# xiao-extension.net
KiCad netlist of a schematic drawn in EAGLE
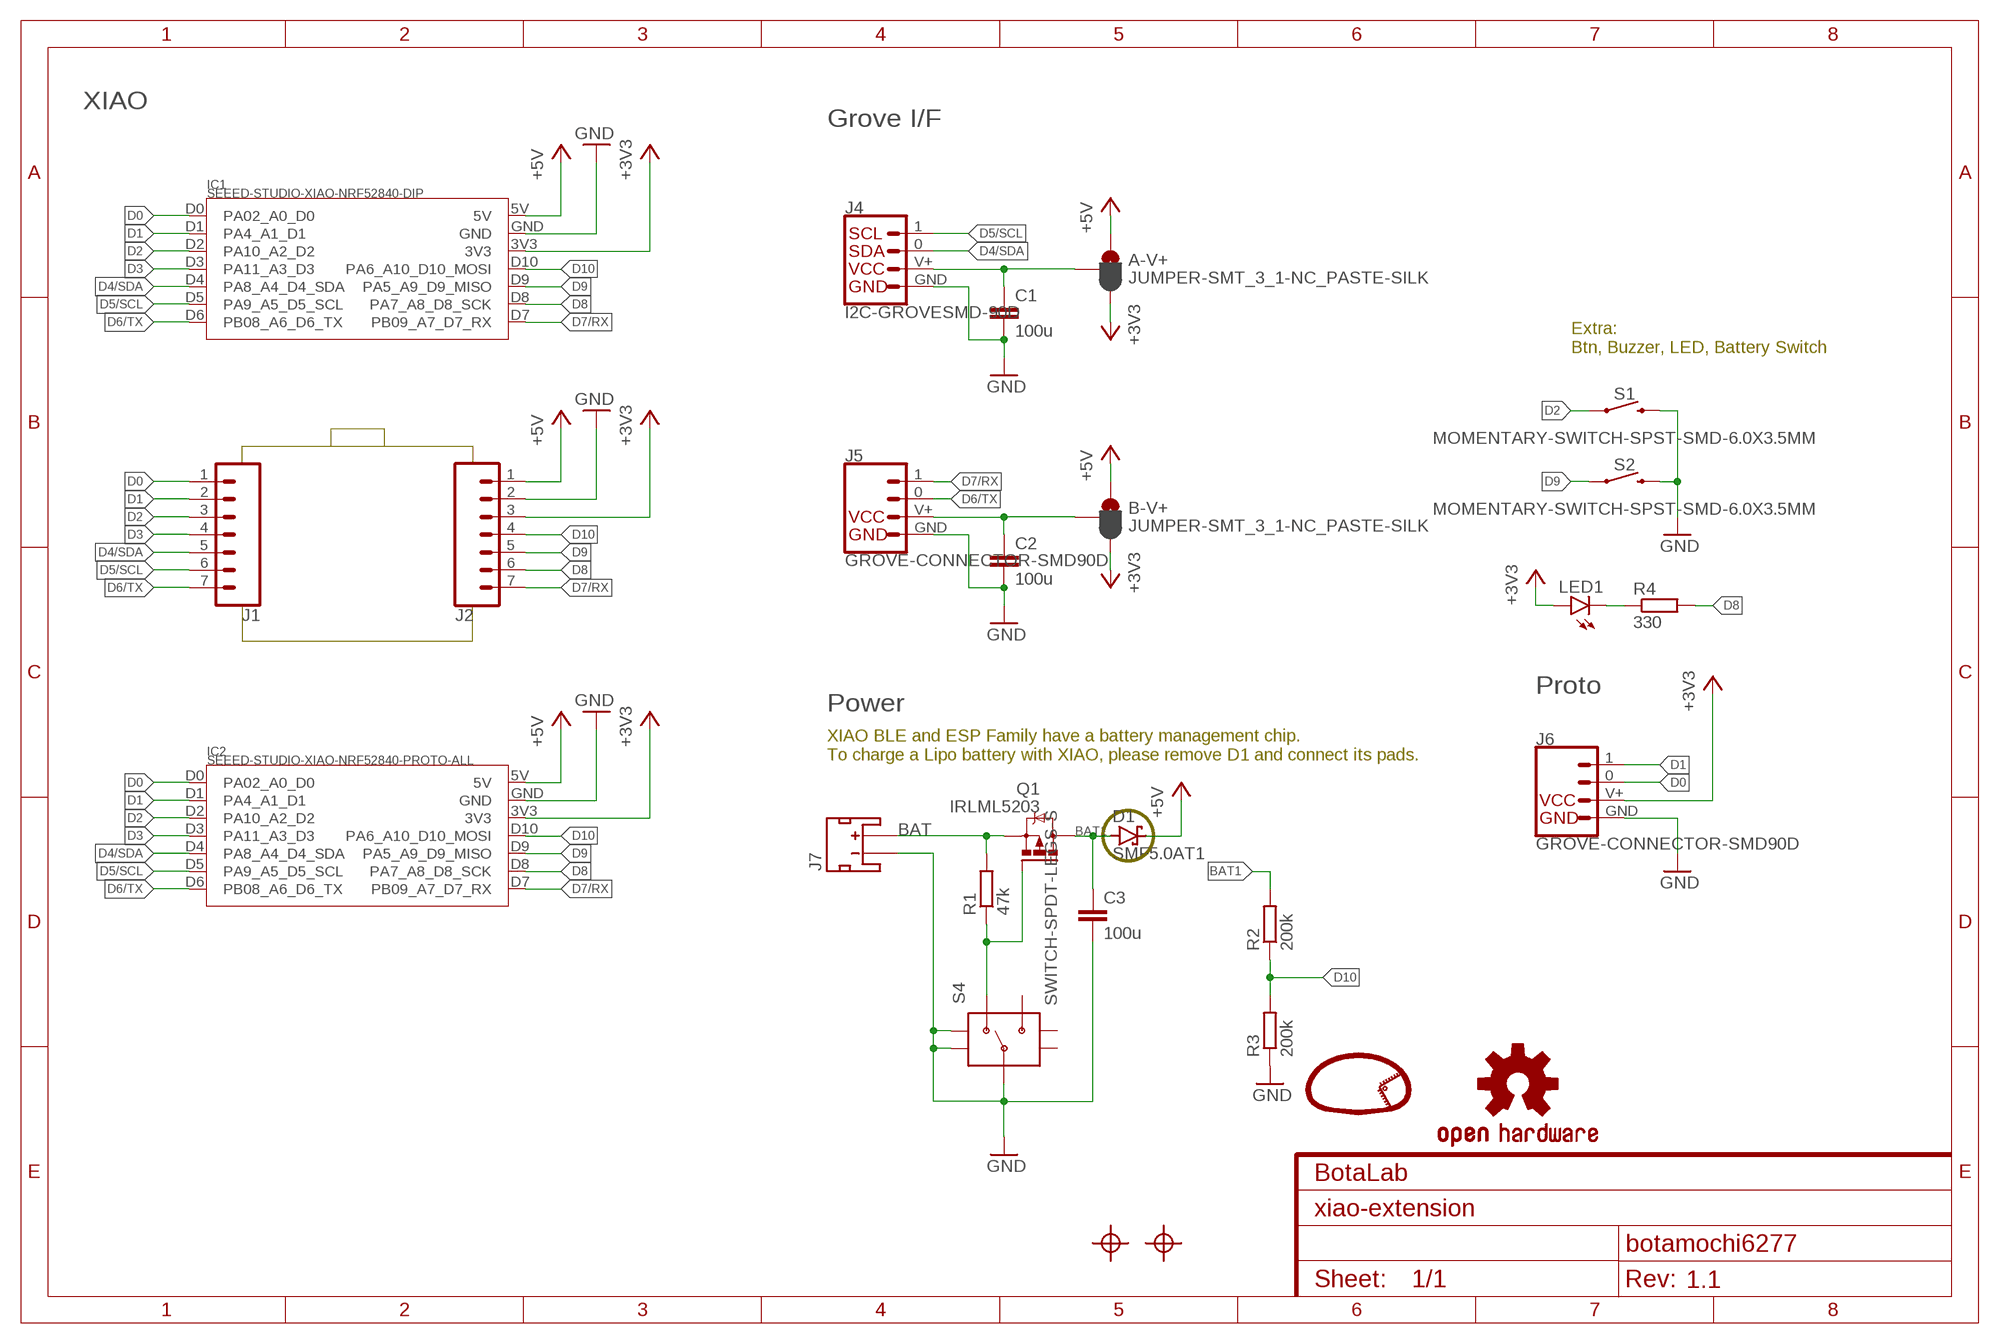
[diagram p0: schematic, sheet 1]

(export (version "E")
  (design (tool "Eeschema 10.0.6"))
  (components
    (comp (ref "A-V+")
      (value "JUMPER-SMT_3_1-NC_PASTE-SILK")
      (footprint "eagle-import:SMT-JUMPER_3_1-NC_PASTE_SILK")
      (libsource (lib "eagle-import") (part "JUMPER-SMT_3_1-NC_PASTE-SILK"))
    )
    (comp (ref "B-V+")
      (value "JUMPER-SMT_3_1-NC_PASTE-SILK")
      (footprint "eagle-import:SMT-JUMPER_3_1-NC_PASTE_SILK")
      (libsource (lib "eagle-import") (part "JUMPER-SMT_3_1-NC_PASTE-SILK"))
    )
    (comp (ref "C1")
      (value "100u")
      (footprint "eagle-import:C3216")
      (libsource (lib "eagle-import") (part "C-EUC3216"))
    )
    (comp (ref "C2")
      (value "100u")
      (footprint "eagle-import:C3216")
      (libsource (lib "eagle-import") (part "C-EUC3216"))
    )
    (comp (ref "C3")
      (value "100u")
      (footprint "eagle-import:C3216")
      (libsource (lib "eagle-import") (part "C-EUC3216"))
    )
    (comp (ref "D1")
      (value "SMF5.0AT1")
      (footprint "eagle-import:SOD123FL")
      (libsource (lib "eagle-import") (part "SMF5.0AT1"))
    )
    (comp (ref "H1")
      (value "HOLE-SILK-2.1")
      (footprint "eagle-import:MOUNTING_HOLE_SILK_2.1")
      (libsource (lib "eagle-import") (part "HOLE-SILK-2.1"))
    )
    (comp (ref "H2")
      (value "HOLE-SILK-2.1")
      (footprint "eagle-import:MOUNTING_HOLE_SILK_2.1")
      (libsource (lib "eagle-import") (part "HOLE-SILK-2.1"))
    )
    (comp (ref "IC1")
      (value "SEEED-STUDIO-XIAO-NRF52840-DIP")
      (footprint "eagle-import:XIAO-NRF52840-DIP")
      (libsource (lib "eagle-import") (part "SEEED-STUDIO-XIAO-NRF52840-DIP"))
    )
    (comp (ref "IC2")
      (value "SEEED-STUDIO-XIAO-NRF52840-PROTO-ALL")
      (footprint "eagle-import:XIAO-SMD-PROTO")
      (libsource (lib "eagle-import") (part "SEEED-STUDIO-XIAO-NRF52840-PROTO-ALL"))
    )
    (comp (ref "J1")
      (value "CONN_07NO_SILK")
      (footprint "eagle-import:1X07_NO_SILK")
      (libsource (lib "eagle-import") (part "CONN_07NO_SILK"))
    )
    (comp (ref "J2")
      (value "CONN_07NO_SILK")
      (footprint "eagle-import:1X07_NO_SILK")
      (libsource (lib "eagle-import") (part "CONN_07NO_SILK"))
    )
    (comp (ref "J4")
      (value "I2C-GROVESMD-90D")
      (footprint "eagle-import:HW4-SMD-2.0-90D")
      (libsource (lib "eagle-import") (part "I2C-GROVESMD-90D"))
    )
    (comp (ref "J5")
      (value "GROVE-CONNECTOR-SMD90D")
      (footprint "eagle-import:HW4-SMD-2.0-90D")
      (libsource (lib "eagle-import") (part "GROVE-CONNECTOR-SMD90D"))
    )
    (comp (ref "J6")
      (value "GROVE-CONNECTOR-SMD90D")
      (footprint "eagle-import:HW4-SMD-2.0-90D")
      (libsource (lib "eagle-import") (part "GROVE-CONNECTOR-SMD90D"))
    )
    (comp (ref "J7")
      (value "JST_2MM_MALE")
      (footprint "eagle-import:JST-2-SMD")
      (libsource (lib "eagle-import") (part "JST_2MM_MALE"))
    )
    (comp (ref "LED1")
      (value "LEDCHIP-LED0603")
      (footprint "eagle-import:CHIP-LED0603")
      (libsource (lib "eagle-import") (part "LEDCHIP-LED0603"))
    )
    (comp (ref "LOGO1")
      (value "LOGO")
      (footprint "eagle-import:LOGO")
      (libsource (lib "eagle-import") (part "LOGO"))
    )
    (comp (ref "LOGO2")
      (value "OSHW-LOGOS")
      (footprint "eagle-import:OSHW-LOGO-S")
      (libsource (lib "eagle-import") (part "OSHW-LOGOS"))
    )
    (comp (ref "Q1")
      (value "IRLML5203")
      (footprint "eagle-import:MICRO3")
      (libsource (lib "eagle-import") (part "IRLML5203"))
    )
    (comp (ref "R1")
      (value "47k")
      (footprint "eagle-import:R0603")
      (libsource (lib "eagle-import") (part "R-EU_R0603"))
    )
    (comp (ref "R2")
      (value "200k")
      (footprint "eagle-import:R0603")
      (libsource (lib "eagle-import") (part "R-EU_R0603"))
    )
    (comp (ref "R3")
      (value "200k")
      (footprint "eagle-import:R0603")
      (libsource (lib "eagle-import") (part "R-EU_R0603"))
    )
    (comp (ref "R4")
      (value "330")
      (footprint "eagle-import:R0603")
      (libsource (lib "eagle-import") (part "R-EU_R0603"))
    )
    (comp (ref "S1")
      (value "MOMENTARY-SWITCH-SPST-SMD-6.0X3.5MM")
      (footprint "eagle-import:TACTILE_SWITCH_SMD_6.0X3.5MM")
      (libsource (lib "eagle-import") (part "MOMENTARY-SWITCH-SPST-SMD-6.0X3.5MM"))
    )
    (comp (ref "S2")
      (value "MOMENTARY-SWITCH-SPST-SMD-6.0X3.5MM")
      (footprint "eagle-import:TACTILE_SWITCH_SMD_6.0X3.5MM")
      (libsource (lib "eagle-import") (part "MOMENTARY-SWITCH-SPST-SMD-6.0X3.5MM"))
    )
    (comp (ref "S4")
      (value "SWITCH-SPDT-LEGS-S")
      (footprint "eagle-import:SWITCH_SPST_SMD_A")
      (libsource (lib "eagle-import") (part "SWITCH-SPDT-LEGS-S"))
    )
  )
  (nets
    (net (code "1") (name "+3V3") (class "Default")
      (node (ref "A-V+") (pin "3") (pinfunction "3_3") (pintype "passive"))
      (node (ref "B-V+") (pin "3") (pinfunction "3_3") (pintype "passive"))
      (node (ref "IC1") (pin "3V3") (pinfunction "3V3_3V3") (pintype "bidirectional"))
      (node (ref "IC2") (pin "3V3") (pinfunction "3V3_3V3") (pintype "bidirectional"))
      (node (ref "J2") (pin "3") (pinfunction "3_3") (pintype "passive"))
      (node (ref "J6") (pin "V+") (pinfunction "VCC_V+") (pintype "power_in"))
      (node (ref "LED1") (pin "A") (pinfunction "A_A") (pintype "passive"))
    )
    (net (code "2") (name "+5V") (class "Default")
      (node (ref "A-V+") (pin "1") (pinfunction "1_1") (pintype "passive"))
      (node (ref "B-V+") (pin "1") (pinfunction "1_1") (pintype "passive"))
      (node (ref "D1") (pin "C") (pinfunction "C_C") (pintype "passive"))
      (node (ref "IC1") (pin "5V") (pinfunction "5V_5V") (pintype "bidirectional"))
      (node (ref "IC2") (pin "5V") (pinfunction "5V_5V") (pintype "bidirectional"))
      (node (ref "J2") (pin "1") (pinfunction "1_1") (pintype "passive"))
    )
    (net (code "3") (name "/BAT") (class "Default")
      (node (ref "J7") (pin "2") (pinfunction "+_2") (pintype "bidirectional"))
      (node (ref "Q1") (pin "2") (pinfunction "S_2") (pintype "passive"))
      (node (ref "R1") (pin "2") (pinfunction "2_2") (pintype "passive"))
    )
    (net (code "4") (name "BAT1") (class "Default")
      (node (ref "C3") (pin "1") (pinfunction "1_1") (pintype "passive"))
      (node (ref "D1") (pin "A") (pinfunction "A_A") (pintype "passive"))
      (node (ref "Q1") (pin "3") (pinfunction "D_3") (pintype "passive"))
      (node (ref "R2") (pin "2") (pinfunction "2_2") (pintype "passive"))
    )
    (net (code "5") (name "D0") (class "Default")
      (node (ref "IC1") (pin "D0") (pinfunction "PA02_A0_D0_D0") (pintype "bidirectional"))
      (node (ref "IC2") (pin "D0") (pinfunction "PA02_A0_D0_D0") (pintype "bidirectional"))
      (node (ref "J1") (pin "1") (pinfunction "1_1") (pintype "passive"))
      (node (ref "J6") (pin "0") (pinfunction "3_0") (pintype "passive"))
    )
    (net (code "6") (name "D1") (class "Default")
      (node (ref "IC1") (pin "D1") (pinfunction "PA4_A1_D1_D1") (pintype "bidirectional"))
      (node (ref "IC2") (pin "D1") (pinfunction "PA4_A1_D1_D1") (pintype "bidirectional"))
      (node (ref "J1") (pin "2") (pinfunction "2_2") (pintype "passive"))
      (node (ref "J6") (pin "1") (pinfunction "4_1") (pintype "passive"))
    )
    (net (code "7") (name "D2") (class "Default")
      (node (ref "IC1") (pin "D2") (pinfunction "PA10_A2_D2_D2") (pintype "bidirectional"))
      (node (ref "IC2") (pin "D2") (pinfunction "PA10_A2_D2_D2") (pintype "bidirectional"))
      (node (ref "J1") (pin "3") (pinfunction "3_3") (pintype "passive"))
      (node (ref "S1") (pin "1") (pinfunction "1_1") (pintype "passive"))
    )
    (net (code "8") (name "D3") (class "Default")
      (node (ref "IC1") (pin "D3") (pinfunction "PA11_A3_D3_D3") (pintype "bidirectional"))
      (node (ref "IC2") (pin "D3") (pinfunction "PA11_A3_D3_D3") (pintype "bidirectional"))
      (node (ref "J1") (pin "4") (pinfunction "4_4") (pintype "passive"))
    )
    (net (code "9") (name "D4{slash}SDA") (class "Default")
      (node (ref "IC1") (pin "D4") (pinfunction "PA8_A4_D4_SDA_D4") (pintype "bidirectional"))
      (node (ref "IC2") (pin "D4") (pinfunction "PA8_A4_D4_SDA_D4") (pintype "bidirectional"))
      (node (ref "J1") (pin "5") (pinfunction "5_5") (pintype "passive"))
      (node (ref "J4") (pin "0") (pinfunction "3_0") (pintype "passive"))
    )
    (net (code "10") (name "D5{slash}SCL") (class "Default")
      (node (ref "IC1") (pin "D5") (pinfunction "PA9_A5_D5_SCL_D5") (pintype "bidirectional"))
      (node (ref "IC2") (pin "D5") (pinfunction "PA9_A5_D5_SCL_D5") (pintype "bidirectional"))
      (node (ref "J1") (pin "6") (pinfunction "6_6") (pintype "passive"))
      (node (ref "J4") (pin "1") (pinfunction "4_1") (pintype "passive"))
    )
    (net (code "11") (name "D6{slash}TX") (class "Default")
      (node (ref "IC1") (pin "D6") (pinfunction "PB08_A6_D6_TX_D6") (pintype "bidirectional"))
      (node (ref "IC2") (pin "D6") (pinfunction "PB08_A6_D6_TX_D6") (pintype "bidirectional"))
      (node (ref "J1") (pin "7") (pinfunction "7_7") (pintype "passive"))
      (node (ref "J5") (pin "0") (pinfunction "3_0") (pintype "passive"))
    )
    (net (code "12") (name "D7{slash}RX") (class "Default")
      (node (ref "IC1") (pin "D7") (pinfunction "PB09_A7_D7_RX_D7") (pintype "bidirectional"))
      (node (ref "IC2") (pin "D7") (pinfunction "PB09_A7_D7_RX_D7") (pintype "bidirectional"))
      (node (ref "J2") (pin "7") (pinfunction "7_7") (pintype "passive"))
      (node (ref "J5") (pin "1") (pinfunction "4_1") (pintype "passive"))
    )
    (net (code "13") (name "D8") (class "Default")
      (node (ref "IC1") (pin "D8") (pinfunction "PA7_A8_D8_SCK_D8") (pintype "bidirectional"))
      (node (ref "IC2") (pin "D8") (pinfunction "PA7_A8_D8_SCK_D8") (pintype "bidirectional"))
      (node (ref "J2") (pin "6") (pinfunction "6_6") (pintype "passive"))
      (node (ref "R4") (pin "2") (pinfunction "2_2") (pintype "passive"))
    )
    (net (code "14") (name "D9") (class "Default")
      (node (ref "IC1") (pin "D9") (pinfunction "PA5_A9_D9_MISO_D9") (pintype "bidirectional"))
      (node (ref "IC2") (pin "D9") (pinfunction "PA5_A9_D9_MISO_D9") (pintype "bidirectional"))
      (node (ref "J2") (pin "5") (pinfunction "5_5") (pintype "passive"))
      (node (ref "S2") (pin "1") (pinfunction "1_1") (pintype "passive"))
    )
    (net (code "15") (name "D10") (class "Default")
      (node (ref "IC1") (pin "D10") (pinfunction "PA6_A10_D10_MOSI_D10") (pintype "bidirectional"))
      (node (ref "IC2") (pin "D10") (pinfunction "PA6_A10_D10_MOSI_D10") (pintype "bidirectional"))
      (node (ref "J2") (pin "4") (pinfunction "4_4") (pintype "passive"))
      (node (ref "R2") (pin "1") (pinfunction "1_1") (pintype "passive"))
      (node (ref "R3") (pin "2") (pinfunction "2_2") (pintype "passive"))
    )
    (net (code "16") (name "GND") (class "Default")
      (node (ref "C1") (pin "2") (pinfunction "2_2") (pintype "passive"))
      (node (ref "C2") (pin "2") (pinfunction "2_2") (pintype "passive"))
      (node (ref "C3") (pin "2") (pinfunction "2_2") (pintype "passive"))
      (node (ref "IC1") (pin "GND") (pinfunction "GND_GND") (pintype "bidirectional"))
      (node (ref "IC2") (pin "GND") (pinfunction "GND_GND") (pintype "bidirectional"))
      (node (ref "J2") (pin "2") (pinfunction "2_2") (pintype "passive"))
      (node (ref "J4") (pin "GND") (pinfunction "1_GND") (pintype "power_in"))
      (node (ref "J5") (pin "GND") (pinfunction "GND_GND") (pintype "power_in"))
      (node (ref "J6") (pin "GND") (pinfunction "GND_GND") (pintype "power_in"))
      (node (ref "J7") (pin "1") (pinfunction "-_1") (pintype "bidirectional"))
      (node (ref "R3") (pin "1") (pinfunction "1_1") (pintype "passive"))
      (node (ref "S1") (pin "2") (pinfunction "2_2") (pintype "passive"))
      (node (ref "S2") (pin "2") (pinfunction "2_2") (pintype "passive"))
      (node (ref "S4") (pin "2") (pinfunction "P_2") (pintype "passive"))
      (node (ref "S4") (pin "L$1") (pinfunction "P$1_L$1") (pintype "passive"))
      (node (ref "S4") (pin "L$2") (pinfunction "P$2_L$2") (pintype "passive"))
    )
    (net (code "17") (name "Net-(J4-2)") (class "Default")
      (node (ref "A-V+") (pin "2") (pinfunction "2_2") (pintype "passive"))
      (node (ref "C1") (pin "1") (pinfunction "1_1") (pintype "passive"))
      (node (ref "J4") (pin "V+") (pinfunction "2_V+") (pintype "power_in"))
    )
    (net (code "18") (name "Net-(J5-VCC)") (class "Default")
      (node (ref "B-V+") (pin "2") (pinfunction "2_2") (pintype "passive"))
      (node (ref "C2") (pin "1") (pinfunction "1_1") (pintype "passive"))
      (node (ref "J5") (pin "V+") (pinfunction "VCC_V+") (pintype "power_in"))
    )
    (net (code "19") (name "Net-(LED1-PadC)") (class "Default")
      (node (ref "LED1") (pin "C") (pinfunction "C_C") (pintype "passive"))
      (node (ref "R4") (pin "1") (pinfunction "1_1") (pintype "passive"))
    )
    (net (code "20") (name "Net-(Q1-G)") (class "Default")
      (node (ref "Q1") (pin "1") (pinfunction "G_1") (pintype "passive"))
      (node (ref "R1") (pin "1") (pinfunction "1_1") (pintype "passive"))
      (node (ref "S4") (pin "1") (pinfunction "O_1") (pintype "passive"))
    )
    (net (code "21") (name "unconnected-(J7-PAD1-PadNC1)") (class "Default")
      (node (ref "J7") (pin "NC1") (pinfunction "PAD1_NC1") (pintype "bidirectional"))
    )
    (net (code "22") (name "unconnected-(J7-PAD2-PadNC2)") (class "Default")
      (node (ref "J7") (pin "NC2") (pinfunction "PAD2_NC2") (pintype "bidirectional"))
    )
    (net (code "23") (name "unconnected-(S4-P$3-PadL$3)") (class "Default")
      (node (ref "S4") (pin "L$3") (pinfunction "P$3_L$3") (pintype "passive"))
    )
    (net (code "24") (name "unconnected-(S4-P$4-PadL$4)") (class "Default")
      (node (ref "S4") (pin "L$4") (pinfunction "P$4_L$4") (pintype "passive"))
    )
    (net (code "25") (name "unconnected-(S4-S-Pad3)") (class "Default")
      (node (ref "S4") (pin "3") (pinfunction "S_3") (pintype "passive"))
    )
  )
)
